# Prototype_schematic.net
KiCad netlist of a schematic drawn in EAGLE
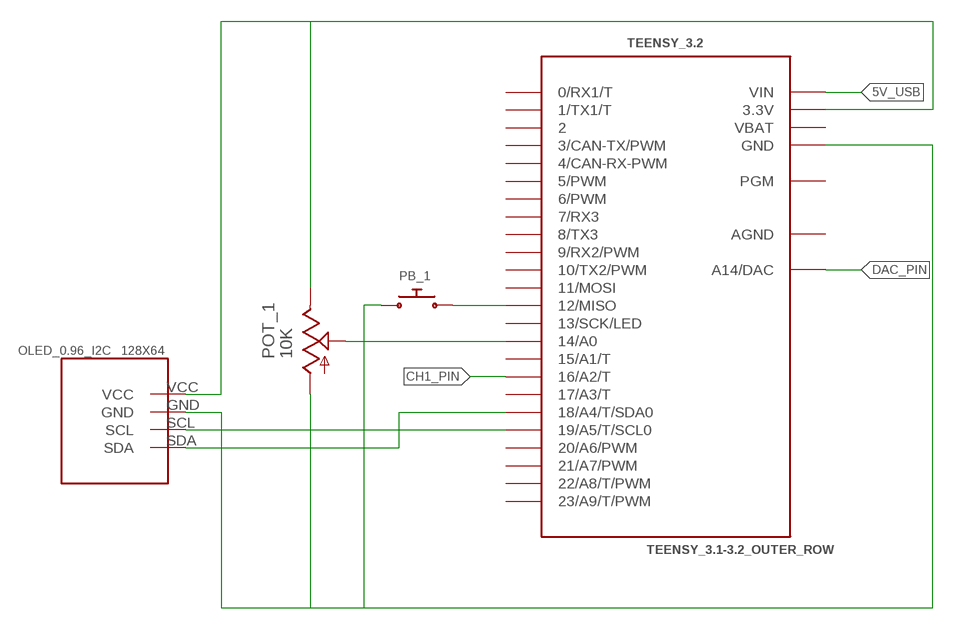
[diagram p0: schematic, sheet 1]

(export (version "E")
  (design (tool "Eeschema 10.0.6"))
  (components
    (comp (ref "128X64")
      (value "OLED_0.96_I2C")
      (footprint "eagle-import:OLED_0.96_I2C")
      (libsource (lib "eagle-import") (part "OLED_0.96_I2C"))
    )
    (comp (ref "PB_1")
      (value "PUSH_BUTTON_RCTNG")
      (footprint "eagle-import:PB_DIP_RCTNG_3-WIDE")
      (libsource (lib "eagle-import") (part "PUSH_BUTTON_RCTNG"))
    )
    (comp (ref "POT_1")
      (value "10K")
      (footprint "eagle-import:POTENTIOMETER")
      (libsource (lib "eagle-import") (part "POTENTIOMETER"))
    )
    (comp (ref "TEENSY_3.2")
      (value "TEENSY_3.1-3.2_OUTER_ROW")
      (footprint "eagle-import:TEENSY_3.0-3.2&LC_OUTER_ROW")
      (libsource (lib "eagle-import") (part "TEENSY_3.1-3.2_OUTER_ROW"))
    )
  )
  (nets
    (net (code "1") (name "/AGND") (class "Default")
      (node (ref "TEENSY_3.2") (pin "AGND") (pinfunction "AGND_AGND") (pintype "power_in"))
    )
    (net (code "2") (name "/VBAT") (class "Default")
      (node (ref "TEENSY_3.2") (pin "VBAT") (pinfunction "VBAT_VBAT") (pintype "power_in"))
    )
    (net (code "3") (name "5V_USB") (class "Default")
      (node (ref "TEENSY_3.2") (pin "VIN") (pinfunction "VIN_VIN") (pintype "power_in"))
    )
    (net (code "4") (name "CH1_PIN") (class "Default")
      (node (ref "TEENSY_3.2") (pin "16/A2") (pinfunction "16/A2/T_16/A2") (pintype "bidirectional"))
    )
    (net (code "5") (name "DAC_PIN") (class "Default")
      (node (ref "TEENSY_3.2") (pin "RESET/DAC") (pinfunction "A14/DAC_RESET/DAC") (pintype "bidirectional"))
    )
    (net (code "6") (name "Net-(PB_1-P$1)") (class "Default")
      (node (ref "128X64") (pin "GND") (pinfunction "GND_GND") (pintype "bidirectional"))
      (node (ref "PB_1") (pin "1") (pinfunction "P$1_1") (pintype "passive"))
      (node (ref "POT_1") (pin "+") (pinfunction "-_+") (pintype "passive"))
      (node (ref "TEENSY_3.2") (pin "GND") (pinfunction "GND_GND") (pintype "power_in"))
      (node (ref "TEENSY_3.2") (pin "GND1") (pinfunction "GND_GND1") (pintype "power_in"))
    )
    (net (code "7") (name "Net-(PB_1-P$2)") (class "Default")
      (node (ref "PB_1") (pin "2") (pinfunction "P$2_2") (pintype "passive"))
      (node (ref "TEENSY_3.2") (pin "12") (pinfunction "12/MISO_12") (pintype "bidirectional"))
    )
    (net (code "8") (name "Net-(POT_1-+)") (class "Default")
      (node (ref "128X64") (pin "VCC") (pinfunction "VCC_VCC") (pintype "bidirectional"))
      (node (ref "POT_1") (pin "-") (pinfunction "+_-") (pintype "passive"))
      (node (ref "TEENSY_3.2") (pin "3.3V") (pinfunction "3.3V_3.3V") (pintype "power_in"))
      (node (ref "TEENSY_3.2") (pin "3.3V1") (pinfunction "3.3V_3.3V1") (pintype "power_in"))
    )
    (net (code "9") (name "Net-(POT_1-PadDATA)") (class "Default")
      (node (ref "POT_1") (pin "DATA") (pinfunction "DATA_DATA") (pintype "passive"))
      (node (ref "TEENSY_3.2") (pin "14/A0") (pinfunction "14/A0_14/A0") (pintype "bidirectional"))
    )
    (net (code "10") (name "Net-(TEENSY_3.2-18{slash}A4{slash}T{slash}SDA0)") (class "Default")
      (node (ref "128X64") (pin "SDA") (pinfunction "SDA_SDA") (pintype "bidirectional"))
      (node (ref "TEENSY_3.2") (pin "18/A4") (pinfunction "18/A4/T/SDA0_18/A4") (pintype "bidirectional"))
    )
    (net (code "11") (name "Net-(TEENSY_3.2-19{slash}A5{slash}T{slash}SCL0)") (class "Default")
      (node (ref "128X64") (pin "SCL") (pinfunction "SCL_SCL") (pintype "bidirectional"))
      (node (ref "TEENSY_3.2") (pin "19/A5") (pinfunction "19/A5/T/SCL0_19/A5") (pintype "bidirectional"))
    )
    (net (code "12") (name "unconnected-(TEENSY_3.2-0{slash}RX1{slash}T-Pad0)") (class "Default")
      (node (ref "TEENSY_3.2") (pin "0") (pinfunction "0/RX1/T_0") (pintype "bidirectional"))
    )
    (net (code "13") (name "unconnected-(TEENSY_3.2-1{slash}TX1{slash}T-Pad1)") (class "Default")
      (node (ref "TEENSY_3.2") (pin "1") (pinfunction "1/TX1/T_1") (pintype "bidirectional"))
    )
    (net (code "14") (name "unconnected-(TEENSY_3.2-3{slash}CAN-TX{slash}PWM-Pad3)") (class "Default")
      (node (ref "TEENSY_3.2") (pin "3") (pinfunction "3/CAN-TX/PWM_3") (pintype "bidirectional"))
    )
    (net (code "15") (name "unconnected-(TEENSY_3.2-4{slash}CAN-RX-PWM-Pad4)") (class "Default")
      (node (ref "TEENSY_3.2") (pin "4") (pinfunction "4/CAN-RX-PWM_4") (pintype "bidirectional"))
    )
    (net (code "16") (name "unconnected-(TEENSY_3.2-5{slash}PWM-Pad5)") (class "Default")
      (node (ref "TEENSY_3.2") (pin "5") (pinfunction "5/PWM_5") (pintype "bidirectional"))
    )
    (net (code "17") (name "unconnected-(TEENSY_3.2-6{slash}PWM-Pad6)") (class "Default")
      (node (ref "TEENSY_3.2") (pin "6") (pinfunction "6/PWM_6") (pintype "bidirectional"))
    )
    (net (code "18") (name "unconnected-(TEENSY_3.2-7{slash}RX3-Pad7)") (class "Default")
      (node (ref "TEENSY_3.2") (pin "7") (pinfunction "7/RX3_7") (pintype "bidirectional"))
    )
    (net (code "19") (name "unconnected-(TEENSY_3.2-8{slash}TX3-Pad8)") (class "Default")
      (node (ref "TEENSY_3.2") (pin "8") (pinfunction "8/TX3_8") (pintype "bidirectional"))
    )
    (net (code "20") (name "unconnected-(TEENSY_3.2-9{slash}RX2{slash}PWM-Pad9)") (class "Default")
      (node (ref "TEENSY_3.2") (pin "9") (pinfunction "9/RX2/PWM_9") (pintype "bidirectional"))
    )
    (net (code "21") (name "unconnected-(TEENSY_3.2-10{slash}TX2{slash}PWM-Pad10)") (class "Default")
      (node (ref "TEENSY_3.2") (pin "10") (pinfunction "10/TX2/PWM_10") (pintype "bidirectional"))
    )
    (net (code "22") (name "unconnected-(TEENSY_3.2-11{slash}MOSI-Pad11)") (class "Default")
      (node (ref "TEENSY_3.2") (pin "11") (pinfunction "11/MOSI_11") (pintype "bidirectional"))
    )
    (net (code "23") (name "unconnected-(TEENSY_3.2-13{slash}SCK{slash}LED-Pad13)") (class "Default")
      (node (ref "TEENSY_3.2") (pin "13") (pinfunction "13/SCK/LED_13") (pintype "bidirectional"))
    )
    (net (code "24") (name "unconnected-(TEENSY_3.2-15{slash}A1{slash}T-Pad15{slash}A1)") (class "Default")
      (node (ref "TEENSY_3.2") (pin "15/A1") (pinfunction "15/A1/T_15/A1") (pintype "bidirectional"))
    )
    (net (code "25") (name "unconnected-(TEENSY_3.2-17{slash}A3{slash}T-Pad17{slash}A3)") (class "Default")
      (node (ref "TEENSY_3.2") (pin "17/A3") (pinfunction "17/A3/T_17/A3") (pintype "bidirectional"))
    )
    (net (code "26") (name "unconnected-(TEENSY_3.2-20{slash}A6{slash}PWM-Pad20{slash}A6)") (class "Default")
      (node (ref "TEENSY_3.2") (pin "20/A6") (pinfunction "20/A6/PWM_20/A6") (pintype "bidirectional"))
    )
    (net (code "27") (name "unconnected-(TEENSY_3.2-21{slash}A7{slash}PWM-Pad21{slash}A7)") (class "Default")
      (node (ref "TEENSY_3.2") (pin "21/A7") (pinfunction "21/A7/PWM_21/A7") (pintype "bidirectional"))
    )
    (net (code "28") (name "unconnected-(TEENSY_3.2-22{slash}A8{slash}T{slash}PWM-Pad22{slash}A8)") (class "Default")
      (node (ref "TEENSY_3.2") (pin "22/A8") (pinfunction "22/A8/T/PWM_22/A8") (pintype "bidirectional"))
    )
    (net (code "29") (name "unconnected-(TEENSY_3.2-23{slash}A9{slash}T{slash}PWM-Pad23{slash}A9)") (class "Default")
      (node (ref "TEENSY_3.2") (pin "23/A9") (pinfunction "23/A9/T/PWM_23/A9") (pintype "bidirectional"))
    )
    (net (code "30") (name "unconnected-(TEENSY_3.2-Pad2)") (class "Default")
      (node (ref "TEENSY_3.2") (pin "2") (pinfunction "2_2") (pintype "bidirectional"))
    )
    (net (code "31") (name "unconnected-(TEENSY_3.2-PadPGM)") (class "Default")
      (node (ref "TEENSY_3.2") (pin "PGM") (pinfunction "PGM_PGM") (pintype "bidirectional"))
    )
  )
)
